# ProProject_CN3791_2024-04-01.net
KiCad netlist of a schematic drawn in EasyEDA Pro
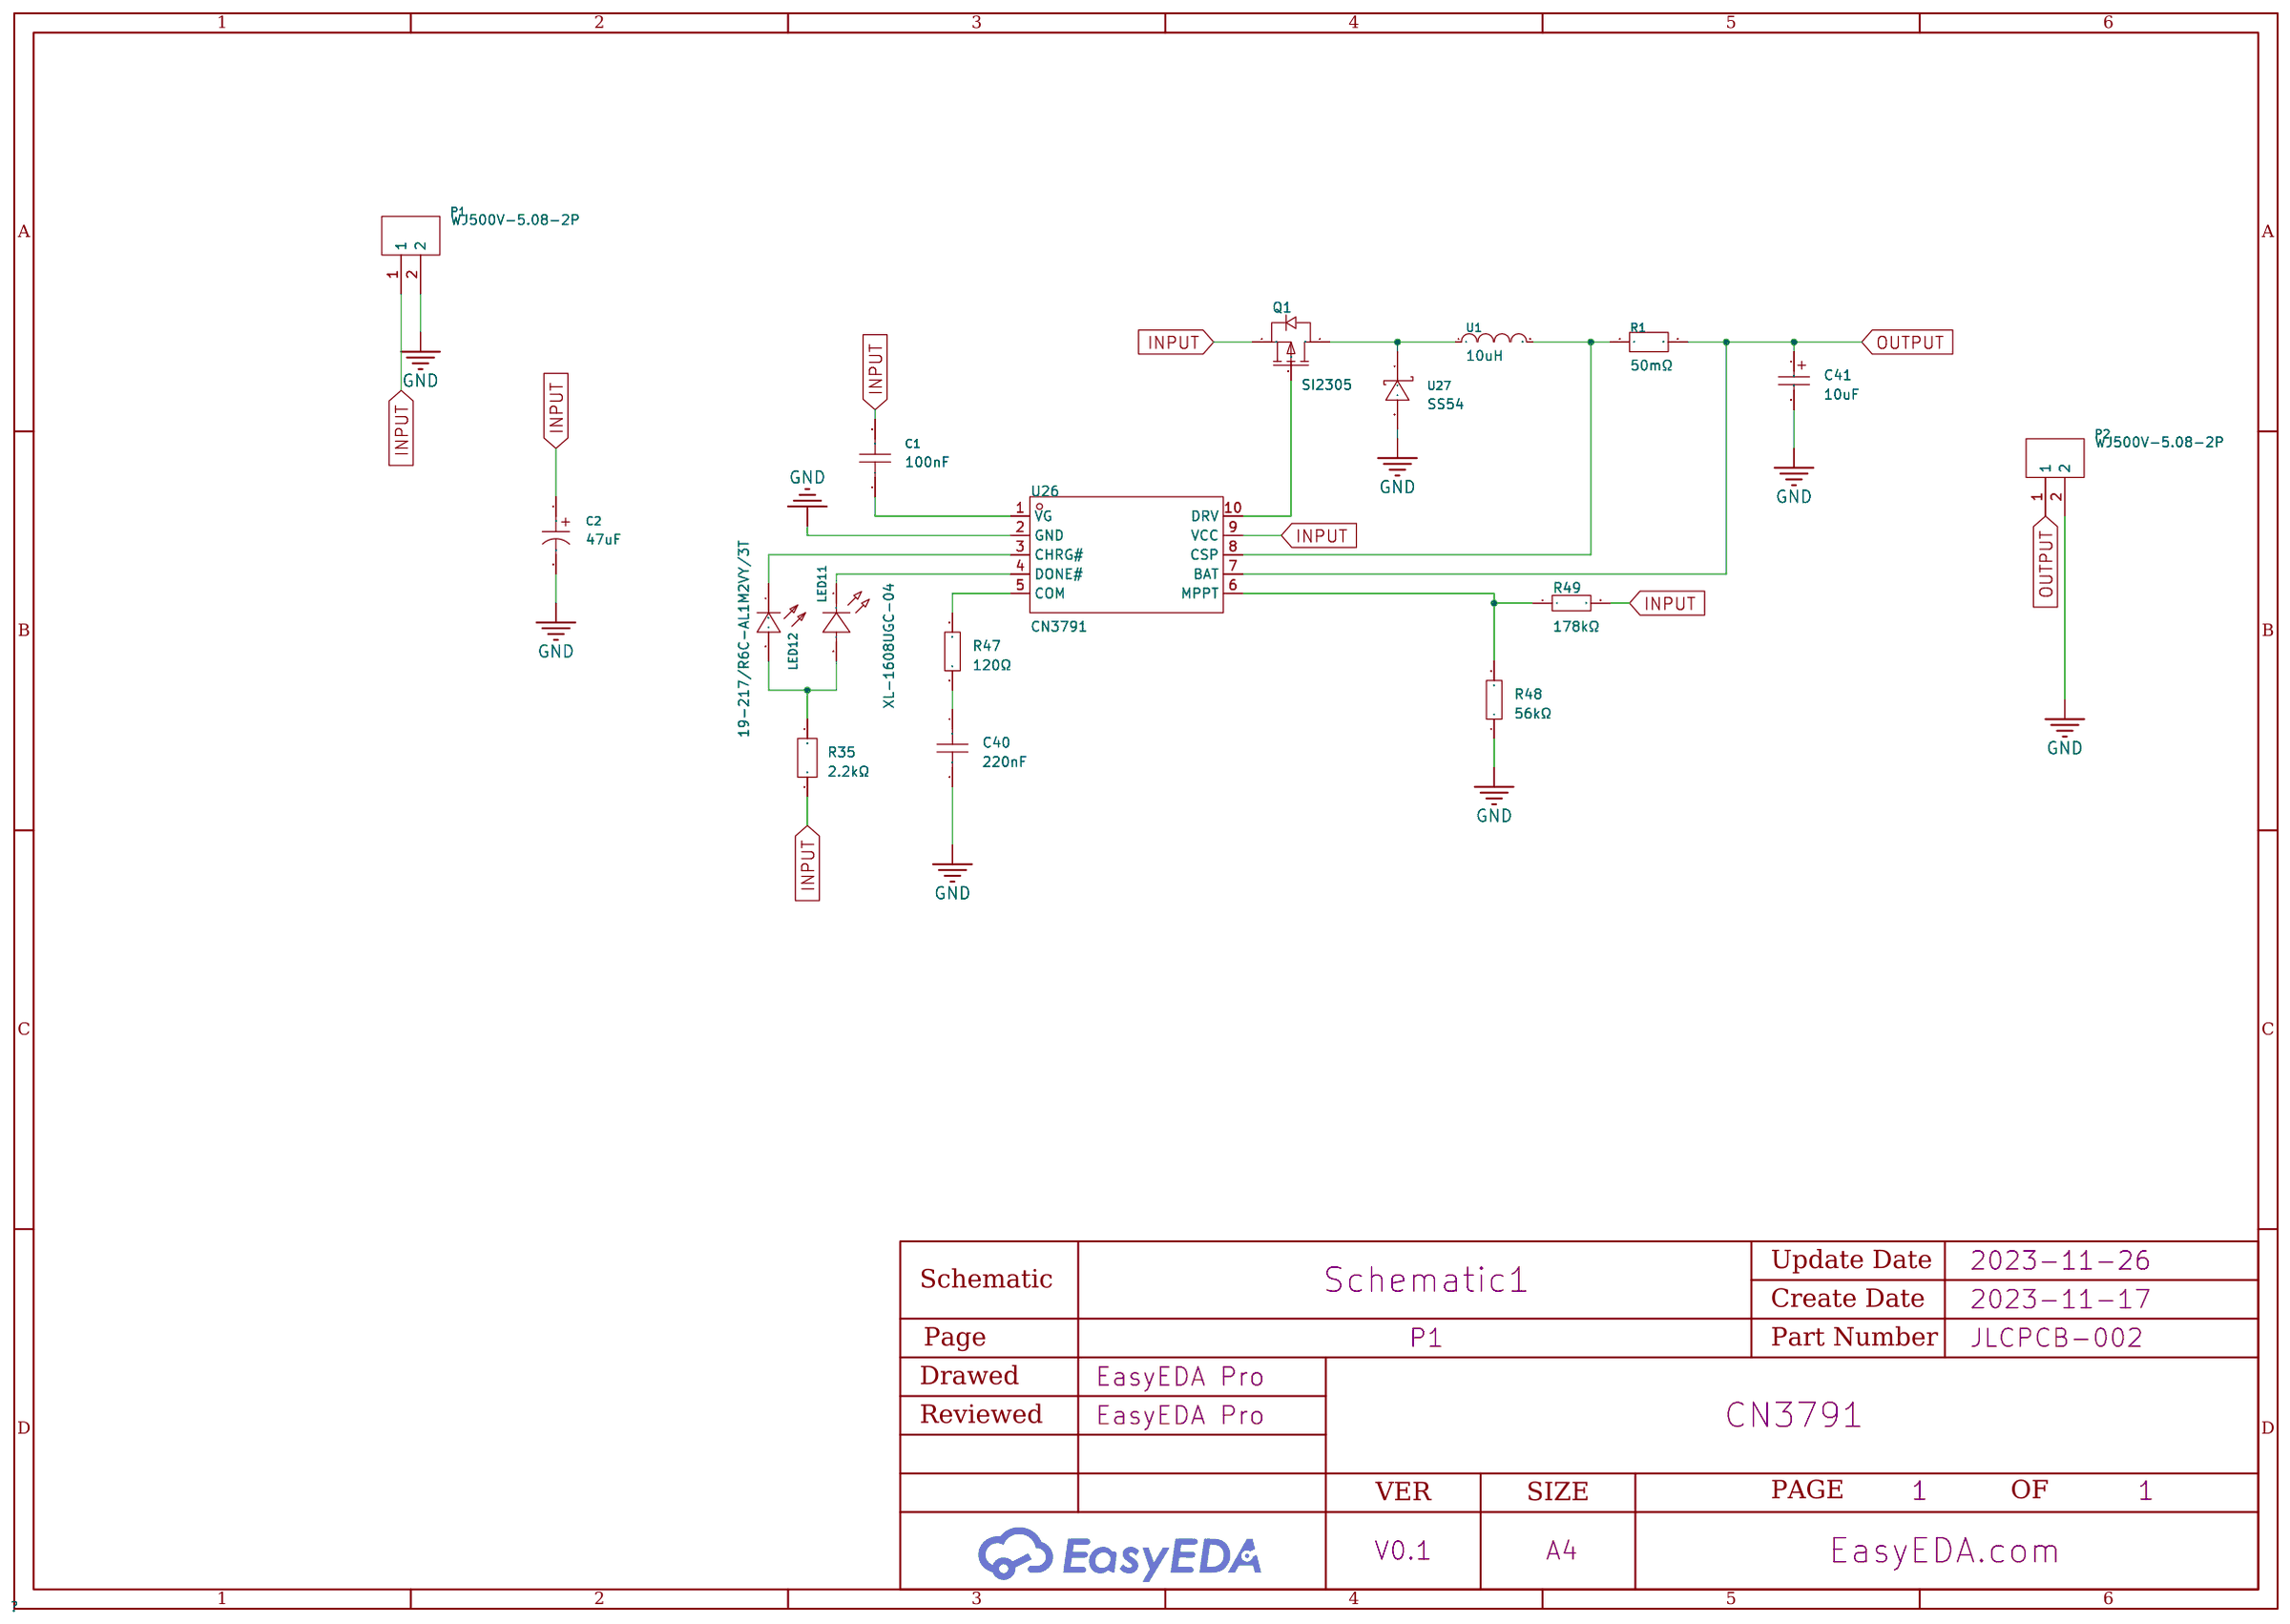
[diagram p0: schematic sheet]

(export (version "E")
  (design (tool "Eeschema 10.0.6"))
  (components
    (comp (ref "C1")
      (value "100nF")
      (footprint "easyedapro:C0402")
      (fields
        (field (name "Manufacturer Part") "CT41G-0402-2X1-16V-0.1μF-K(N)")
        (field (name "Manufacturer") "TORCH(火炬)")
      )
      (libsource (lib "easyedapro") (part "CT41G-0402-2X1-16V-0.1μF-K(N)"))
    )
    (comp (ref "C2")
      (value "47uF")
      (footprint "easyedapro:CAP-SMD_BD6.3-L6.6-W6.6-LS7.6-FD")
      (fields
        (field (name "Manufacturer Part") "RVT47UF50V67RV0029")
        (field (name "Manufacturer") "KNSCHA(科尼盛)")
      )
      (libsource (lib "easyedapro") (part "RVT47UF50V67RV0029"))
    )
    (comp (ref "C40")
      (value "220nF")
      (footprint "easyedapro:C0402")
      (fields (field (name "Manufacturer Part") "0402B224K160NT") (field (name "Manufacturer") "FH(风华)"))
      (libsource (lib "easyedapro") (part "0402B224K160NT"))
    )
    (comp (ref "C41")
      (value "10uF")
      (footprint "easyedapro:CAP-SMD_L3.2-W1.6-RD")
      (fields
        (field (name "Manufacturer Part") "CA45-A-16V-10uF-K")
        (field (name "Manufacturer") "CEC(振华新云)")
      )
      (libsource (lib "easyedapro") (part "CA45-A-16V-10UF-K"))
    )
    (comp (ref "LED11")
      (value "XL-1608UGC-04")
      (footprint "easyedapro:LED0603-RD_GREEN")
      (fields (field (name "Manufacturer") "XINGLIGHT(成兴光)"))
      (libsource (lib "easyedapro") (part "XL-1608UGC-04"))
    )
    (comp (ref "LED12")
      (value "19-217/R6C-AL1M2VY/3T")
      (footprint "easyedapro:LED0603-RD")
      (fields (field (name "Manufacturer") "EVERLIGHT(亿光)"))
      (libsource (lib "easyedapro") (part "19-217/R6C-AL1M2VY/3T"))
    )
    (comp (ref "P1")
      (value "WJ500V-5.08-2P")
      (footprint "easyedapro:CONN-TH_2P-P5.00_WJ500V-5.08-2P")
      (fields (field (name "Manufacturer") "KANGNEX(康奈克斯电气)"))
      (libsource (lib "easyedapro") (part "WJ500V-5.08-2P-14-00A"))
    )
    (comp (ref "P2")
      (value "WJ500V-5.08-2P")
      (footprint "easyedapro:CONN-TH_2P-P5.00_WJ500V-5.08-2P")
      (fields (field (name "Manufacturer") "KANGNEX(康奈克斯电气)"))
      (libsource (lib "easyedapro") (part "WJ500V-5.08-2P-14-00A"))
    )
    (comp (ref "Q1")
      (value "SI2305")
      (footprint "easyedapro:SOT-23-3_L2.9-W1.3-P1.90-LS2.4-BR")
      (fields (field (name "Manufacturer") "YONGYUTAI(永裕泰)"))
      (libsource (lib "easyedapro") (part "SI2305_C2909911"))
    )
    (comp (ref "R1")
      (value "50mΩ")
      (footprint "easyedapro:R1206")
      (fields (field (name "Manufacturer Part") "FRL1206JR050TS") (field (name "Manufacturer") "FOJAN(富捷)"))
      (libsource (lib "easyedapro") (part "FRL1206JR050TS"))
    )
    (comp (ref "R35")
      (value "2.2kΩ")
      (footprint "easyedapro:R2010")
      (fields
        (field (name "Manufacturer Part") "201007J0222T4E")
        (field (name "Manufacturer") "UNI-ROYAL(厚声)")
      )
      (libsource (lib "easyedapro") (part "201007J0222T4E"))
    )
    (comp (ref "R47")
      (value "120Ω")
      (footprint "easyedapro:R0402")
      (fields (field (name "Manufacturer Part") "RC0402FR-07120RL") (field (name "Manufacturer") "YAGEO(国巨)"))
      (libsource (lib "easyedapro") (part "RC0402FR-07120RL"))
    )
    (comp (ref "R48")
      (value "56kΩ")
      (footprint "easyedapro:R0402")
      (fields (field (name "Manufacturer Part") "RC0402FR-0756KL") (field (name "Manufacturer") "YAGEO(国巨)"))
      (libsource (lib "easyedapro") (part "RC0402FR-0756KL"))
    )
    (comp (ref "R49")
      (value "178kΩ")
      (footprint "easyedapro:R0402")
      (fields (field (name "Manufacturer Part") "RM04FTN1783") (field (name "Manufacturer") "大毅科技"))
      (libsource (lib "easyedapro") (part "RM04FTN1783"))
    )
    (comp (ref "U1")
      (value "10uH")
      (footprint "easyedapro:IND-SMD_L7.2-W6.6_GPSR07X0")
      (fields (field (name "Manufacturer Part") "CYA0630-10UH") (field (name "Manufacturer") "SHOU HAN(首韩)"))
      (libsource (lib "easyedapro") (part "CYA0630-10UH"))
    )
    (comp (ref "U26")
      (value "CN3791")
      (footprint "easyedapro:SSOP-10_L4.9-W3.9-P1.00-LS6.0-BL")
      (fields (field (name "Manufacturer") "CONSONANCE(上海如韵)"))
      (libsource (lib "easyedapro") (part "CN3791"))
    )
    (comp (ref "U27")
      (value "SS54")
      (footprint "easyedapro:SMC_L6.9-W5.9-LS7.9-RD")
      (fields (field (name "Manufacturer") "晶扬电子"))
      (libsource (lib "easyedapro") (part "SS54_C5307984"))
    )
  )
  (nets
    (net (code "1") (name "GND") (class "Default")
      (node (ref "C2") (pin "2") (pinfunction "2_2") (pintype "input"))
      (node (ref "C40") (pin "2") (pinfunction "2_2") (pintype "input"))
      (node (ref "C41") (pin "2") (pinfunction "2_2") (pintype "input"))
      (node (ref "P1") (pin "2") (pinfunction "2_2") (pintype "input"))
      (node (ref "P2") (pin "2") (pinfunction "2_2") (pintype "input"))
      (node (ref "R48") (pin "1") (pinfunction "1_1") (pintype "input"))
      (node (ref "U26") (pin "2") (pinfunction "GND_2") (pintype "input"))
      (node (ref "U27") (pin "2") (pinfunction "A_2") (pintype "input"))
    )
    (net (code "2") (name "INPUT") (class "Default")
      (node (ref "C1") (pin "2") (pinfunction "2_2") (pintype "input"))
      (node (ref "C2") (pin "1") (pinfunction "1_1") (pintype "input"))
      (node (ref "P1") (pin "1") (pinfunction "1_1") (pintype "input"))
      (node (ref "Q1") (pin "2") (pinfunction "S_2") (pintype "input"))
      (node (ref "R35") (pin "2") (pinfunction "2_2") (pintype "input"))
      (node (ref "R49") (pin "2") (pinfunction "2_2") (pintype "input"))
      (node (ref "U26") (pin "9") (pinfunction "VCC_9") (pintype "input"))
    )
    (net (code "3") (name "Net-(C40-Pad1)") (class "Default")
      (node (ref "C40") (pin "1") (pinfunction "1_1") (pintype "input"))
      (node (ref "R47") (pin "1") (pinfunction "1_1") (pintype "input"))
    )
    (net (code "4") (name "Net-(LED11-A)") (class "Default")
      (node (ref "LED11") (pin "2") (pinfunction "A_2") (pintype "input"))
      (node (ref "LED12") (pin "2") (pinfunction "A_2") (pintype "input"))
      (node (ref "R35") (pin "1") (pinfunction "1_1") (pintype "input"))
    )
    (net (code "5") (name "Net-(LED11-K)") (class "Default")
      (node (ref "LED11") (pin "1") (pinfunction "K_1") (pintype "input"))
      (node (ref "U26") (pin "4") (pinfunction "DONE#_4") (pintype "input"))
    )
    (net (code "6") (name "Net-(LED12-C)") (class "Default")
      (node (ref "LED12") (pin "1") (pinfunction "C_1") (pintype "input"))
      (node (ref "U26") (pin "3") (pinfunction "CHRG#_3") (pintype "input"))
    )
    (net (code "7") (name "Net-(Q1-D)") (class "Default")
      (node (ref "Q1") (pin "3") (pinfunction "D_3") (pintype "input"))
      (node (ref "U1") (pin "1") (pinfunction "1_1") (pintype "input"))
      (node (ref "U27") (pin "1") (pinfunction "K_1") (pintype "input"))
    )
    (net (code "8") (name "Net-(Q1-G)") (class "Default")
      (node (ref "Q1") (pin "1") (pinfunction "G_1") (pintype "input"))
      (node (ref "U26") (pin "10") (pinfunction "DRV_10") (pintype "input"))
    )
    (net (code "9") (name "Net-(U26-COM)") (class "Default")
      (node (ref "R47") (pin "2") (pinfunction "2_2") (pintype "input"))
      (node (ref "U26") (pin "5") (pinfunction "COM_5") (pintype "input"))
    )
    (net (code "10") (name "Net-(U26-CSP)") (class "Default")
      (node (ref "R1") (pin "1") (pinfunction "1_1") (pintype "input"))
      (node (ref "U1") (pin "2") (pinfunction "2_2") (pintype "input"))
      (node (ref "U26") (pin "8") (pinfunction "CSP_8") (pintype "input"))
    )
    (net (code "11") (name "Net-(U26-MPPT)") (class "Default")
      (node (ref "R48") (pin "2") (pinfunction "2_2") (pintype "input"))
      (node (ref "R49") (pin "1") (pinfunction "1_1") (pintype "input"))
      (node (ref "U26") (pin "6") (pinfunction "MPPT_6") (pintype "input"))
    )
    (net (code "12") (name "Net-(U26-VG)") (class "Default")
      (node (ref "C1") (pin "1") (pinfunction "1_1") (pintype "input"))
      (node (ref "U26") (pin "1") (pinfunction "VG_1") (pintype "input"))
    )
    (net (code "13") (name "OUTPUT") (class "Default")
      (node (ref "C41") (pin "1") (pinfunction "1_1") (pintype "input"))
      (node (ref "P2") (pin "1") (pinfunction "1_1") (pintype "input"))
      (node (ref "R1") (pin "2") (pinfunction "2_2") (pintype "input"))
      (node (ref "U26") (pin "7") (pinfunction "BAT_7") (pintype "input"))
    )
  )
)
